# Hugo3D.net
KiCad netlist of a schematic drawn in Altium Designer
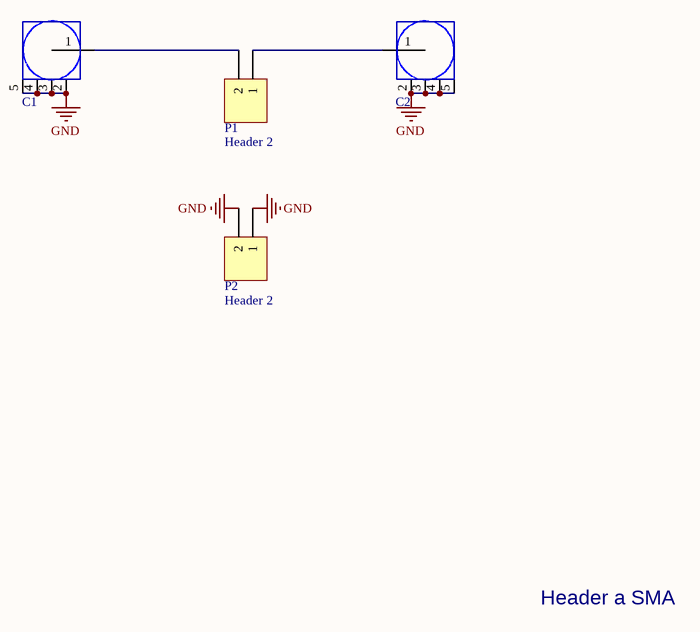
[diagram p0: Hugo3D.SchDoc]

(export (version "E")
  (design (tool "Eeschema 10.0.6"))
  (components
    (comp (ref "C1") (value "SMA") (footprint "SMA2-pequeño") (libsource (lib "epf") (part "SMA")))
    (comp (ref "C2") (value "SMA") (footprint "SMA2-pequeño") (libsource (lib "") (part "SMA_1")))
    (comp (ref "P1")
      (value "Header 2")
      (footprint "Header2_Vertical")
      (description "Header, 2-Pin")
      (fields (field (name "PUBLISHER") "Altium Limited"))
      (libsource (lib "Miscellaneous Connectors") (part "Header 2"))
    )
    (comp (ref "P2")
      (value "Header 2")
      (footprint "Header2_Vertical")
      (description "Header, 2-Pin")
      (fields (field (name "PUBLISHER") "Altium Limited"))
      (libsource (lib "Miscellaneous Connectors") (part "Header 2"))
    )
  )
  (nets
    (net (code "1") (name "GND") (class "Default")
      (node (ref "C1") (pin "2") (pinfunction "GND_2") (pintype "passive"))
      (node (ref "C1") (pin "3") (pinfunction "GND_3") (pintype "passive"))
      (node (ref "C1") (pin "4") (pinfunction "GND_4") (pintype "passive"))
      (node (ref "C1") (pin "5") (pinfunction "GND_5") (pintype "passive"))
      (node (ref "C2") (pin "2") (pinfunction "GND_2") (pintype "passive"))
      (node (ref "C2") (pin "3") (pinfunction "GND_3") (pintype "passive"))
      (node (ref "C2") (pin "4") (pinfunction "GND_4") (pintype "passive"))
      (node (ref "C2") (pin "5") (pinfunction "GND_5") (pintype "passive"))
      (node (ref "P2") (pin "1") (pinfunction "1_1") (pintype "passive"))
      (node (ref "P2") (pin "2") (pinfunction "2_2") (pintype "passive"))
    )
    (net (code "2") (name "Net-(C1-RF)") (class "Default")
      (node (ref "C1") (pin "1") (pinfunction "RF_1") (pintype "passive"))
      (node (ref "P1") (pin "2") (pinfunction "2_2") (pintype "passive"))
    )
    (net (code "3") (name "Net-(C2-RF)") (class "Default")
      (node (ref "C2") (pin "1") (pinfunction "RF_1") (pintype "passive"))
      (node (ref "P1") (pin "1") (pinfunction "1_1") (pintype "passive"))
    )
  )
)
